# 120V_ESO.net
KiCad netlist of a schematic drawn in EAGLE
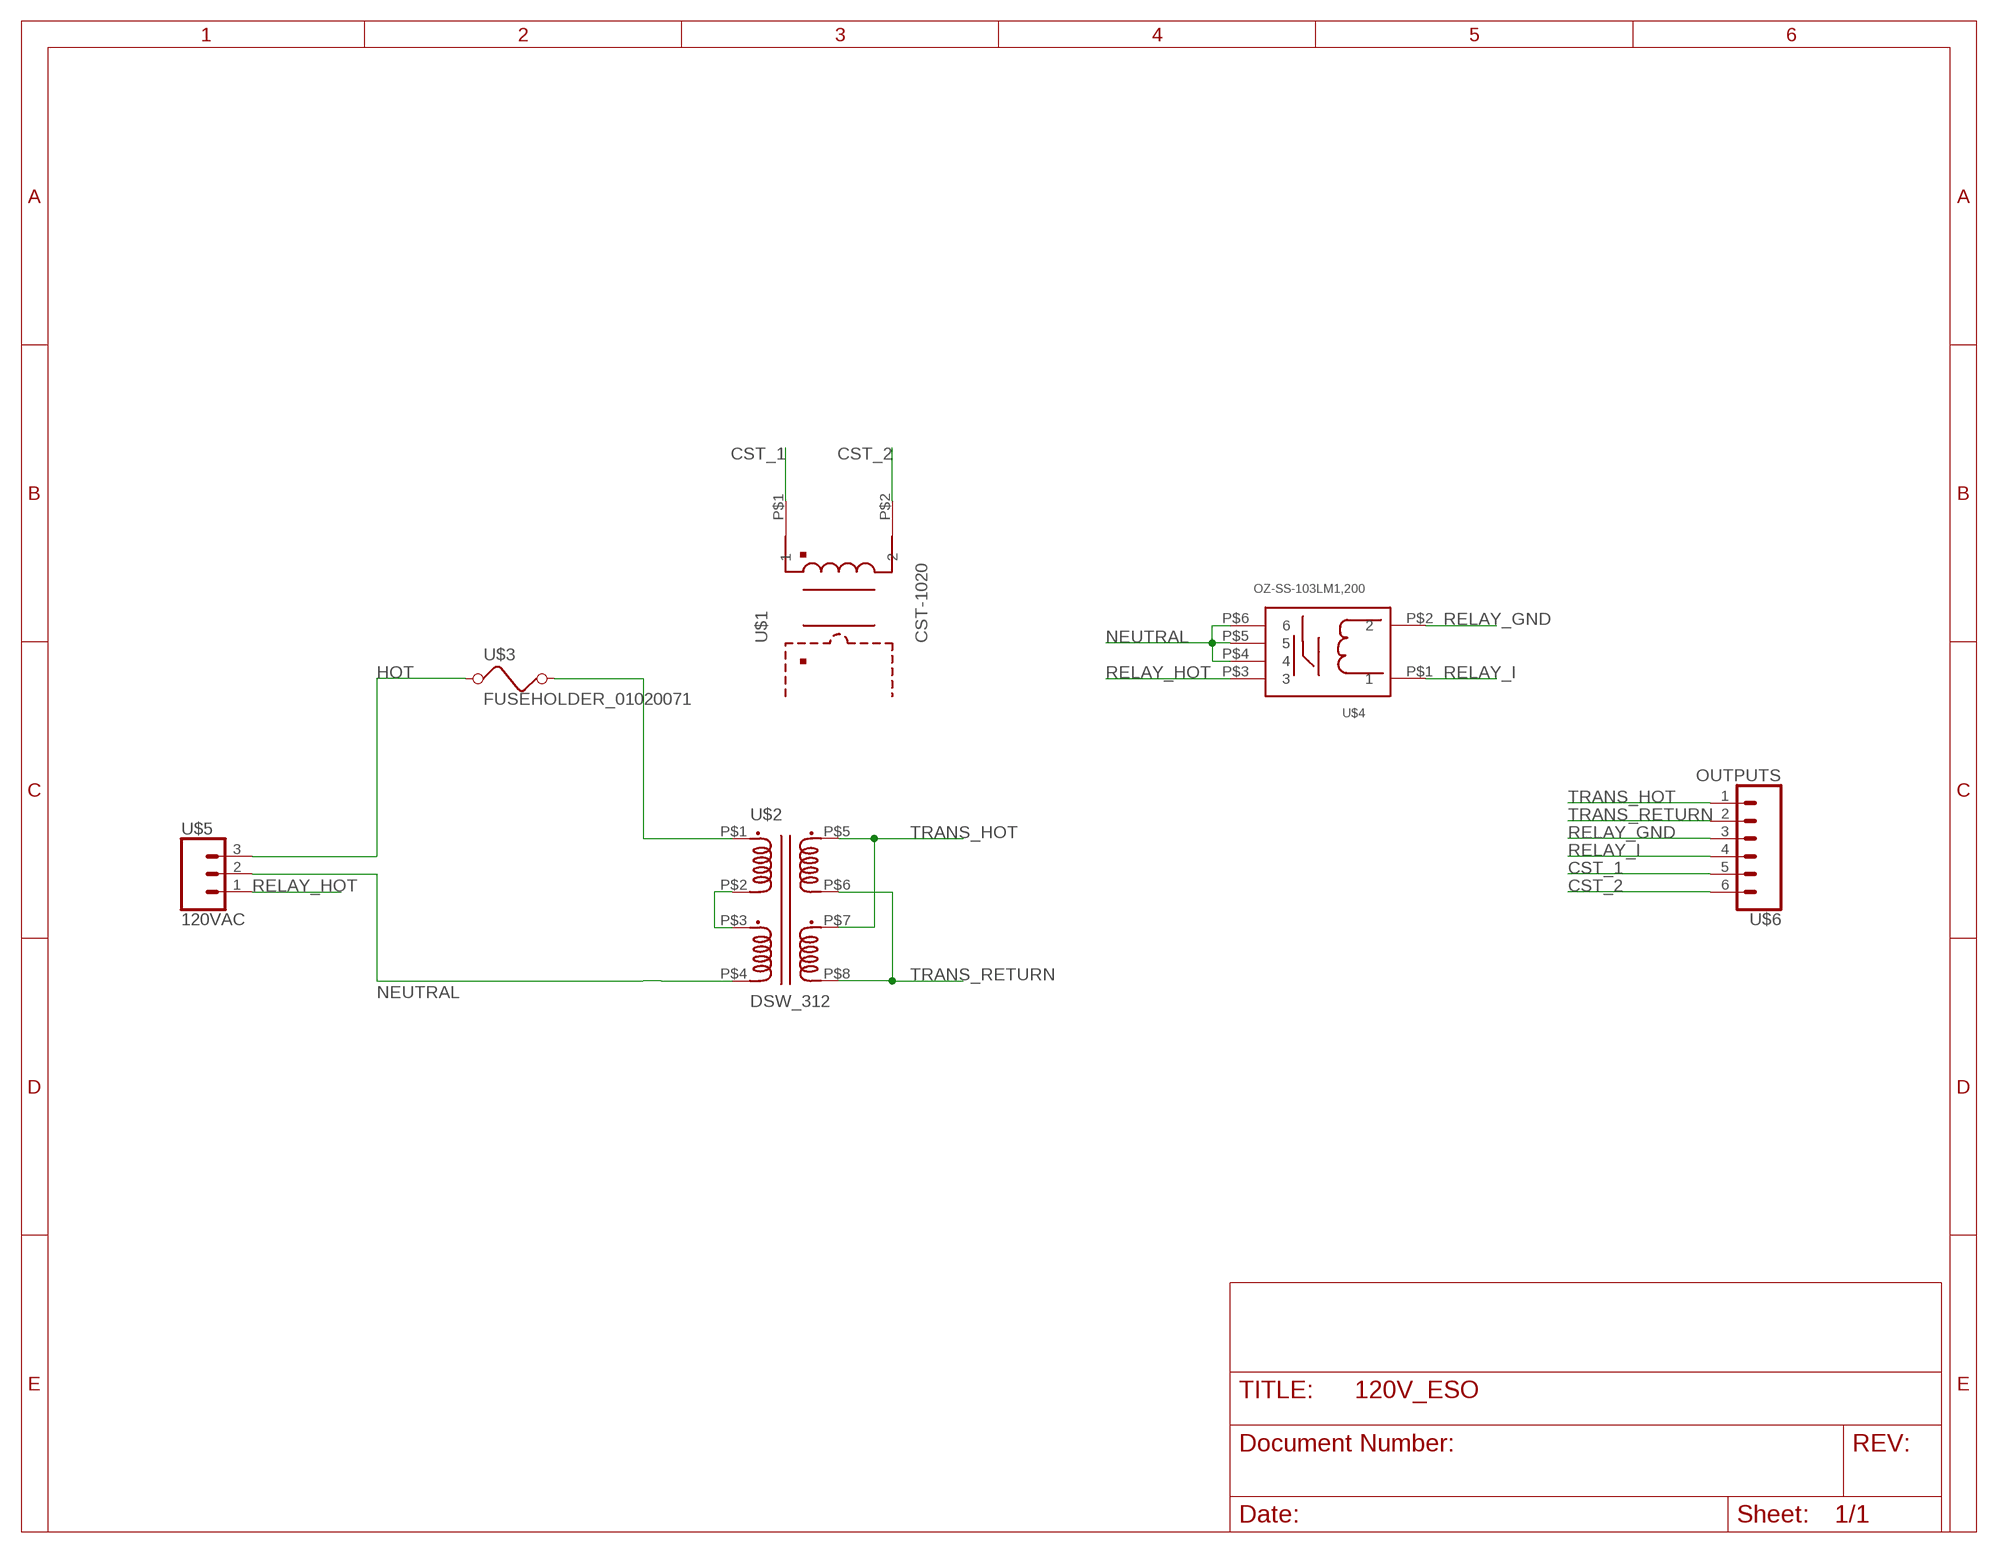
[diagram p0: schematic, sheet 1]

(export (version "E")
  (design (tool "Eeschema 10.0.6"))
  (components
    (comp (ref "U$1")
      (value "CST-1020")
      (footprint "eagle-import:CST-1020")
      (libsource (lib "eagle-import") (part "CST-1020"))
    )
    (comp (ref "U$2")
      (value "DSW_312")
      (footprint "eagle-import:DSW_312")
      (libsource (lib "eagle-import") (part "DSW_312"))
    )
    (comp (ref "U$3")
      (value "FUSEHOLDER_01020071")
      (footprint "eagle-import:FUSEHOLDER_01020071Z")
      (libsource (lib "eagle-import") (part "FUSEHOLDER_01020071"))
    )
    (comp (ref "U$4")
      (value "OZ-SS-103LM1,200")
      (footprint "eagle-import:OZ-SS-103LM1,200")
      (libsource (lib "eagle-import") (part "OZ-SS-103LM1,200"))
    )
    (comp (ref "U$5")
      (value "120VAC")
      (footprint "eagle-import:1X03")
      (libsource (lib "eagle-import") (part "120VAC"))
    )
    (comp (ref "U$6")
      (value "OUTPUTS")
      (footprint "eagle-import:1X06")
      (libsource (lib "eagle-import") (part "OUTPUTS"))
    )
  )
  (nets
    (net (code "1") (name "/CST_1") (class "Default")
      (node (ref "U$1") (pin "P$1") (pinfunction "1_P$1") (pintype "bidirectional"))
      (node (ref "U$6") (pin "5") (pinfunction "5_5") (pintype "passive"))
    )
    (net (code "2") (name "/CST_2") (class "Default")
      (node (ref "U$1") (pin "P$2") (pinfunction "2_P$2") (pintype "bidirectional"))
      (node (ref "U$6") (pin "6") (pinfunction "6_6") (pintype "passive"))
    )
    (net (code "3") (name "/HOT") (class "Default")
      (node (ref "U$3") (pin "P$1") (pinfunction "1_P$1") (pintype "passive"))
      (node (ref "U$3") (pin "P$2") (pinfunction "1_P$2") (pintype "passive"))
      (node (ref "U$5") (pin "3") (pinfunction "3_3") (pintype "passive"))
    )
    (net (code "4") (name "/NEUTRAL") (class "Default")
      (node (ref "U$2") (pin "P$4") (pinfunction "P2.2_P$4") (pintype "passive"))
      (node (ref "U$4") (pin "P$4") (pinfunction "4_P$4") (pintype "bidirectional"))
      (node (ref "U$4") (pin "P$5") (pinfunction "5_P$5") (pintype "bidirectional"))
      (node (ref "U$4") (pin "P$6") (pinfunction "6_P$6") (pintype "bidirectional"))
      (node (ref "U$5") (pin "2") (pinfunction "2_2") (pintype "passive"))
    )
    (net (code "5") (name "/RELAY_GND") (class "Default")
      (node (ref "U$4") (pin "P$2") (pinfunction "2_P$2") (pintype "bidirectional"))
      (node (ref "U$6") (pin "3") (pinfunction "3_3") (pintype "passive"))
    )
    (net (code "6") (name "/RELAY_HOT") (class "Default")
      (node (ref "U$4") (pin "P$3") (pinfunction "3_P$3") (pintype "bidirectional"))
      (node (ref "U$5") (pin "1") (pinfunction "1_1") (pintype "passive"))
    )
    (net (code "7") (name "/RELAY_I") (class "Default")
      (node (ref "U$4") (pin "P$1") (pinfunction "1_P$1") (pintype "bidirectional"))
      (node (ref "U$6") (pin "4") (pinfunction "4_4") (pintype "passive"))
    )
    (net (code "8") (name "/TRANS_HOT") (class "Default")
      (node (ref "U$2") (pin "P$5") (pinfunction "S1.1_P$5") (pintype "passive"))
      (node (ref "U$2") (pin "P$7") (pinfunction "S2.1_P$7") (pintype "passive"))
      (node (ref "U$6") (pin "1") (pinfunction "1_1") (pintype "passive"))
    )
    (net (code "9") (name "/TRANS_RETURN") (class "Default")
      (node (ref "U$2") (pin "P$6") (pinfunction "S1.2_P$6") (pintype "passive"))
      (node (ref "U$2") (pin "P$8") (pinfunction "S2.2_P$8") (pintype "passive"))
      (node (ref "U$6") (pin "2") (pinfunction "2_2") (pintype "passive"))
    )
    (net (code "10") (name "Net-(U$2-P1.1)") (class "Default")
      (node (ref "U$2") (pin "P$1") (pinfunction "P1.1_P$1") (pintype "passive"))
      (node (ref "U$3") (pin "P$3") (pinfunction "2_P$3") (pintype "passive"))
      (node (ref "U$3") (pin "P$4") (pinfunction "2_P$4") (pintype "passive"))
    )
    (net (code "11") (name "Net-(U$2-P1.2)") (class "Default")
      (node (ref "U$2") (pin "P$2") (pinfunction "P1.2_P$2") (pintype "passive"))
      (node (ref "U$2") (pin "P$3") (pinfunction "P2.1_P$3") (pintype "passive"))
    )
  )
)
